# 1-Schematic.net
KiCad netlist of a schematic drawn in EasyEDA
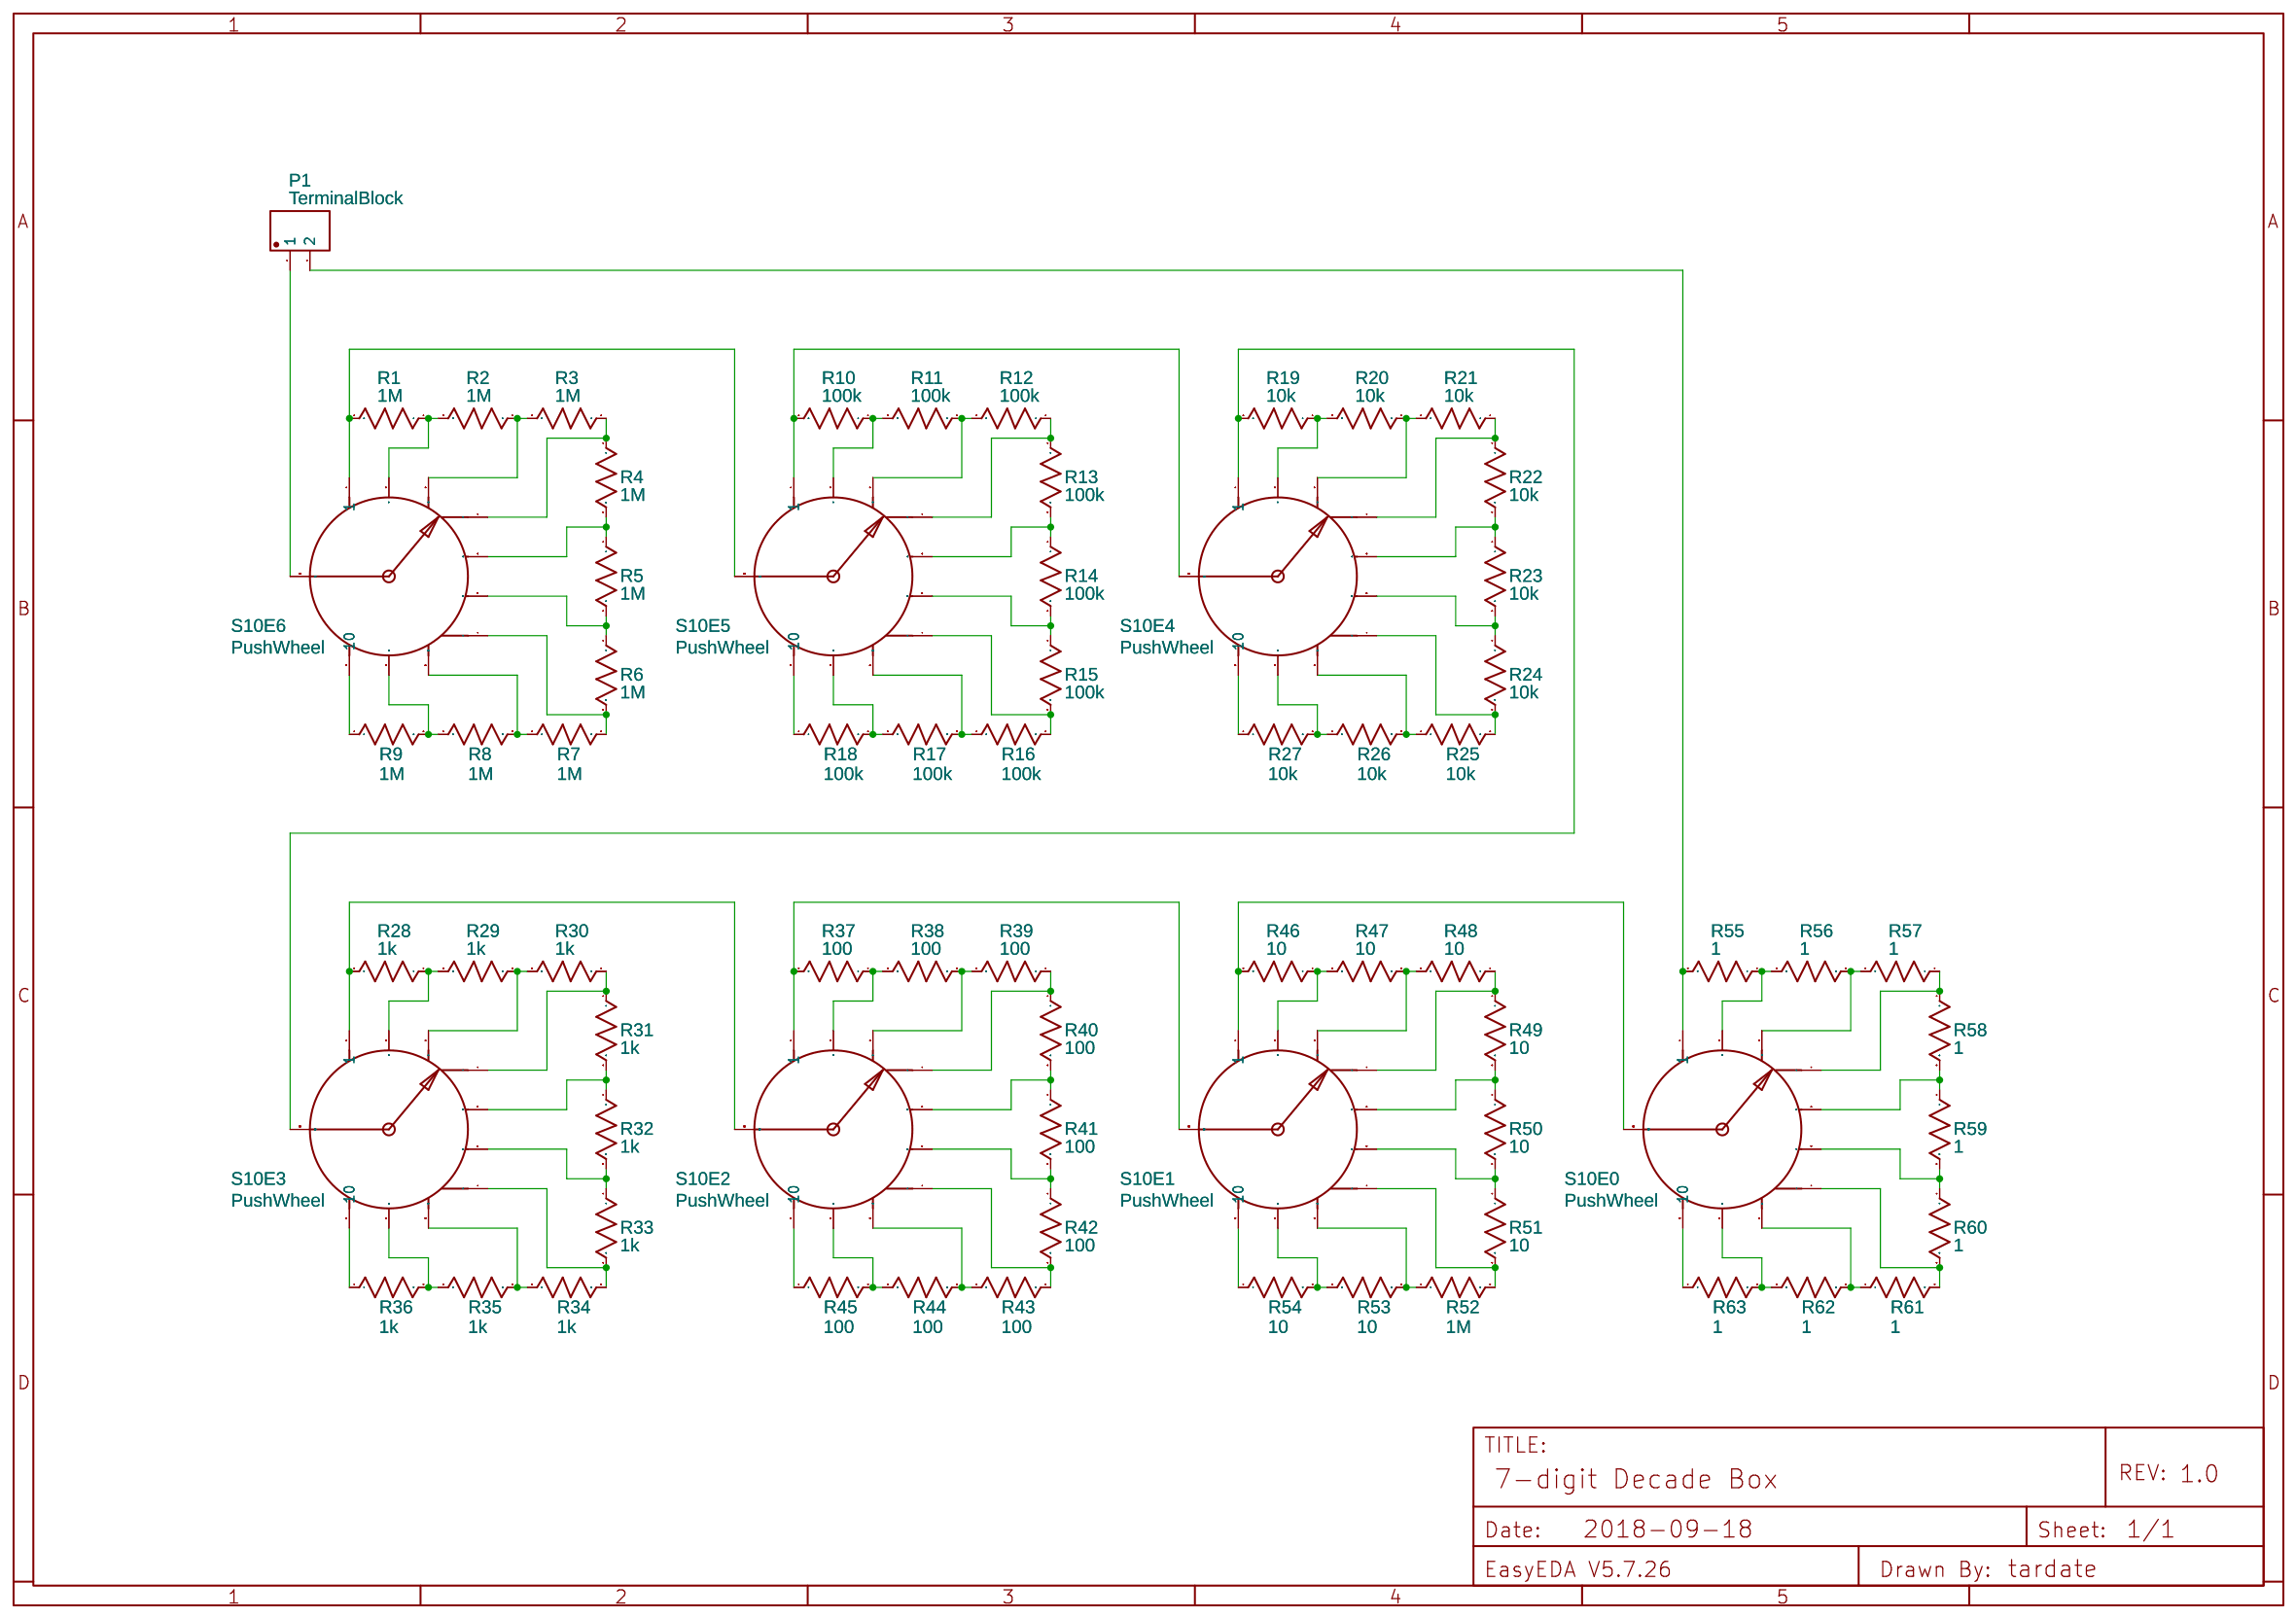
[diagram p0: schematic sheet]

(export (version "E")
  (design (tool "Eeschema 10.0.6"))
  (components
    (comp (ref "P1")
      (value "TerminalBlock")
      (fields
        (field (name "BOM_Manufacturer Part") "WJ2EDGVC-5.08-2P")
        (field (name "BOM_Supplier Part") "C8445")
      )
      (libsource (lib "") (part "Unknown_145_115"))
    )
    (comp (ref "R1")
      (value "1M")
      (fields (field (name "BOM_Manufacturer Part") "?"))
      (libsource (lib "") (part "Res_AXIAL-0.3(1/8W)_US"))
    )
    (comp (ref "R2")
      (value "1M")
      (fields (field (name "BOM_Manufacturer Part") "?"))
      (libsource (lib "") (part "Res_AXIAL-0.3(1/8W)_US"))
    )
    (comp (ref "R3")
      (value "1M")
      (fields (field (name "BOM_Manufacturer Part") "?"))
      (libsource (lib "") (part "Res_AXIAL-0.3(1/8W)_US"))
    )
    (comp (ref "R4")
      (value "1M")
      (fields (field (name "BOM_Manufacturer Part") "?"))
      (libsource (lib "") (part "Res_AXIAL-0.3(1/8W)_US_2"))
    )
    (comp (ref "R5")
      (value "1M")
      (fields (field (name "BOM_Manufacturer Part") "?"))
      (libsource (lib "") (part "Res_AXIAL-0.3(1/8W)_US_2"))
    )
    (comp (ref "R6")
      (value "1M")
      (fields (field (name "BOM_Manufacturer Part") "?"))
      (libsource (lib "") (part "Res_AXIAL-0.3(1/8W)_US_2"))
    )
    (comp (ref "R7")
      (value "1M")
      (fields (field (name "BOM_Manufacturer Part") "?"))
      (libsource (lib "") (part "Res_AXIAL-0.3(1/8W)_US_1"))
    )
    (comp (ref "R8")
      (value "1M")
      (fields (field (name "BOM_Manufacturer Part") "?"))
      (libsource (lib "") (part "Res_AXIAL-0.3(1/8W)_US_1"))
    )
    (comp (ref "R9")
      (value "1M")
      (fields (field (name "BOM_Manufacturer Part") "?"))
      (libsource (lib "") (part "Res_AXIAL-0.3(1/8W)_US_1"))
    )
    (comp (ref "R10")
      (value "100k")
      (fields (field (name "BOM_Manufacturer Part") "?"))
      (libsource (lib "") (part "Res_AXIAL-0.3(1/8W)_US"))
    )
    (comp (ref "R11")
      (value "100k")
      (fields (field (name "BOM_Manufacturer Part") "?"))
      (libsource (lib "") (part "Res_AXIAL-0.3(1/8W)_US"))
    )
    (comp (ref "R12")
      (value "100k")
      (fields (field (name "BOM_Manufacturer Part") "?"))
      (libsource (lib "") (part "Res_AXIAL-0.3(1/8W)_US"))
    )
    (comp (ref "R13")
      (value "100k")
      (fields (field (name "BOM_Manufacturer Part") "?"))
      (libsource (lib "") (part "Res_AXIAL-0.3(1/8W)_US_2"))
    )
    (comp (ref "R14")
      (value "100k")
      (fields (field (name "BOM_Manufacturer Part") "?"))
      (libsource (lib "") (part "Res_AXIAL-0.3(1/8W)_US_2"))
    )
    (comp (ref "R15")
      (value "100k")
      (fields (field (name "BOM_Manufacturer Part") "?"))
      (libsource (lib "") (part "Res_AXIAL-0.3(1/8W)_US_2"))
    )
    (comp (ref "R16")
      (value "100k")
      (fields (field (name "BOM_Manufacturer Part") "?"))
      (libsource (lib "") (part "Res_AXIAL-0.3(1/8W)_US_1"))
    )
    (comp (ref "R17")
      (value "100k")
      (fields (field (name "BOM_Manufacturer Part") "?"))
      (libsource (lib "") (part "Res_AXIAL-0.3(1/8W)_US_1"))
    )
    (comp (ref "R18")
      (value "100k")
      (fields (field (name "BOM_Manufacturer Part") "?"))
      (libsource (lib "") (part "Res_AXIAL-0.3(1/8W)_US_1"))
    )
    (comp (ref "R19")
      (value "10k")
      (fields (field (name "BOM_Manufacturer Part") "?"))
      (libsource (lib "") (part "Res_AXIAL-0.3(1/8W)_US"))
    )
    (comp (ref "R20")
      (value "10k")
      (fields (field (name "BOM_Manufacturer Part") "?"))
      (libsource (lib "") (part "Res_AXIAL-0.3(1/8W)_US"))
    )
    (comp (ref "R21")
      (value "10k")
      (fields (field (name "BOM_Manufacturer Part") "?"))
      (libsource (lib "") (part "Res_AXIAL-0.3(1/8W)_US"))
    )
    (comp (ref "R22")
      (value "10k")
      (fields (field (name "BOM_Manufacturer Part") "?"))
      (libsource (lib "") (part "Res_AXIAL-0.3(1/8W)_US_2"))
    )
    (comp (ref "R23")
      (value "10k")
      (fields (field (name "BOM_Manufacturer Part") "?"))
      (libsource (lib "") (part "Res_AXIAL-0.3(1/8W)_US_2"))
    )
    (comp (ref "R24")
      (value "10k")
      (fields (field (name "BOM_Manufacturer Part") "?"))
      (libsource (lib "") (part "Res_AXIAL-0.3(1/8W)_US_2"))
    )
    (comp (ref "R25")
      (value "10k")
      (fields (field (name "BOM_Manufacturer Part") "?"))
      (libsource (lib "") (part "Res_AXIAL-0.3(1/8W)_US_1"))
    )
    (comp (ref "R26")
      (value "10k")
      (fields (field (name "BOM_Manufacturer Part") "?"))
      (libsource (lib "") (part "Res_AXIAL-0.3(1/8W)_US_1"))
    )
    (comp (ref "R27")
      (value "10k")
      (fields (field (name "BOM_Manufacturer Part") "?"))
      (libsource (lib "") (part "Res_AXIAL-0.3(1/8W)_US_1"))
    )
    (comp (ref "R28")
      (value "1k")
      (fields (field (name "BOM_Manufacturer Part") "?"))
      (libsource (lib "") (part "Res_AXIAL-0.3(1/8W)_US"))
    )
    (comp (ref "R29")
      (value "1k")
      (fields (field (name "BOM_Manufacturer Part") "?"))
      (libsource (lib "") (part "Res_AXIAL-0.3(1/8W)_US"))
    )
    (comp (ref "R30")
      (value "1k")
      (fields (field (name "BOM_Manufacturer Part") "?"))
      (libsource (lib "") (part "Res_AXIAL-0.3(1/8W)_US"))
    )
    (comp (ref "R31")
      (value "1k")
      (fields (field (name "BOM_Manufacturer Part") "?"))
      (libsource (lib "") (part "Res_AXIAL-0.3(1/8W)_US_2"))
    )
    (comp (ref "R32")
      (value "1k")
      (fields (field (name "BOM_Manufacturer Part") "?"))
      (libsource (lib "") (part "Res_AXIAL-0.3(1/8W)_US_2"))
    )
    (comp (ref "R33")
      (value "1k")
      (fields (field (name "BOM_Manufacturer Part") "?"))
      (libsource (lib "") (part "Res_AXIAL-0.3(1/8W)_US_2"))
    )
    (comp (ref "R34")
      (value "1k")
      (fields (field (name "BOM_Manufacturer Part") "?"))
      (libsource (lib "") (part "Res_AXIAL-0.3(1/8W)_US_1"))
    )
    (comp (ref "R35")
      (value "1k")
      (fields (field (name "BOM_Manufacturer Part") "?"))
      (libsource (lib "") (part "Res_AXIAL-0.3(1/8W)_US_1"))
    )
    (comp (ref "R36")
      (value "1k")
      (fields (field (name "BOM_Manufacturer Part") "?"))
      (libsource (lib "") (part "Res_AXIAL-0.3(1/8W)_US_1"))
    )
    (comp (ref "R37")
      (value "100")
      (fields (field (name "BOM_Manufacturer Part") "?"))
      (libsource (lib "") (part "Res_AXIAL-0.3(1/8W)_US"))
    )
    (comp (ref "R38")
      (value "100")
      (fields (field (name "BOM_Manufacturer Part") "?"))
      (libsource (lib "") (part "Res_AXIAL-0.3(1/8W)_US"))
    )
    (comp (ref "R39")
      (value "100")
      (fields (field (name "BOM_Manufacturer Part") "?"))
      (libsource (lib "") (part "Res_AXIAL-0.3(1/8W)_US"))
    )
    (comp (ref "R40")
      (value "100")
      (fields (field (name "BOM_Manufacturer Part") "?"))
      (libsource (lib "") (part "Res_AXIAL-0.3(1/8W)_US_2"))
    )
    (comp (ref "R41")
      (value "100")
      (fields (field (name "BOM_Manufacturer Part") "?"))
      (libsource (lib "") (part "Res_AXIAL-0.3(1/8W)_US_2"))
    )
    (comp (ref "R42")
      (value "100")
      (fields (field (name "BOM_Manufacturer Part") "?"))
      (libsource (lib "") (part "Res_AXIAL-0.3(1/8W)_US_2"))
    )
    (comp (ref "R43")
      (value "100")
      (fields (field (name "BOM_Manufacturer Part") "?"))
      (libsource (lib "") (part "Res_AXIAL-0.3(1/8W)_US_1"))
    )
    (comp (ref "R44")
      (value "100")
      (fields (field (name "BOM_Manufacturer Part") "?"))
      (libsource (lib "") (part "Res_AXIAL-0.3(1/8W)_US_1"))
    )
    (comp (ref "R45")
      (value "100")
      (fields (field (name "BOM_Manufacturer Part") "?"))
      (libsource (lib "") (part "Res_AXIAL-0.3(1/8W)_US_1"))
    )
    (comp (ref "R46")
      (value "10")
      (fields (field (name "BOM_Manufacturer Part") "?"))
      (libsource (lib "") (part "Res_AXIAL-0.3(1/8W)_US"))
    )
    (comp (ref "R47")
      (value "10")
      (fields (field (name "BOM_Manufacturer Part") "?"))
      (libsource (lib "") (part "Res_AXIAL-0.3(1/8W)_US"))
    )
    (comp (ref "R48")
      (value "10")
      (fields (field (name "BOM_Manufacturer Part") "?"))
      (libsource (lib "") (part "Res_AXIAL-0.3(1/8W)_US"))
    )
    (comp (ref "R49")
      (value "10")
      (fields (field (name "BOM_Manufacturer Part") "?"))
      (libsource (lib "") (part "Res_AXIAL-0.3(1/8W)_US_2"))
    )
    (comp (ref "R50")
      (value "10")
      (fields (field (name "BOM_Manufacturer Part") "?"))
      (libsource (lib "") (part "Res_AXIAL-0.3(1/8W)_US_2"))
    )
    (comp (ref "R51")
      (value "10")
      (fields (field (name "BOM_Manufacturer Part") "?"))
      (libsource (lib "") (part "Res_AXIAL-0.3(1/8W)_US_2"))
    )
    (comp (ref "R52")
      (value "1M")
      (fields (field (name "BOM_Manufacturer Part") "?"))
      (libsource (lib "") (part "Res_AXIAL-0.3(1/8W)_US_1"))
    )
    (comp (ref "R53")
      (value "10")
      (fields (field (name "BOM_Manufacturer Part") "?"))
      (libsource (lib "") (part "Res_AXIAL-0.3(1/8W)_US_1"))
    )
    (comp (ref "R54")
      (value "10")
      (fields (field (name "BOM_Manufacturer Part") "?"))
      (libsource (lib "") (part "Res_AXIAL-0.3(1/8W)_US_1"))
    )
    (comp (ref "R55")
      (value "1")
      (fields (field (name "BOM_Manufacturer Part") "?"))
      (libsource (lib "") (part "Res_AXIAL-0.3(1/8W)_US"))
    )
    (comp (ref "R56")
      (value "1")
      (fields (field (name "BOM_Manufacturer Part") "?"))
      (libsource (lib "") (part "Res_AXIAL-0.3(1/8W)_US"))
    )
    (comp (ref "R57")
      (value "1")
      (fields (field (name "BOM_Manufacturer Part") "?"))
      (libsource (lib "") (part "Res_AXIAL-0.3(1/8W)_US"))
    )
    (comp (ref "R58")
      (value "1")
      (fields (field (name "BOM_Manufacturer Part") "?"))
      (libsource (lib "") (part "Res_AXIAL-0.3(1/8W)_US_2"))
    )
    (comp (ref "R59")
      (value "1")
      (fields (field (name "BOM_Manufacturer Part") "?"))
      (libsource (lib "") (part "Res_AXIAL-0.3(1/8W)_US_2"))
    )
    (comp (ref "R60")
      (value "1")
      (fields (field (name "BOM_Manufacturer Part") "?"))
      (libsource (lib "") (part "Res_AXIAL-0.3(1/8W)_US_2"))
    )
    (comp (ref "R61")
      (value "1")
      (fields (field (name "BOM_Manufacturer Part") "?"))
      (libsource (lib "") (part "Res_AXIAL-0.3(1/8W)_US_1"))
    )
    (comp (ref "R62")
      (value "1")
      (fields (field (name "BOM_Manufacturer Part") "?"))
      (libsource (lib "") (part "Res_AXIAL-0.3(1/8W)_US_1"))
    )
    (comp (ref "R63")
      (value "1")
      (fields (field (name "BOM_Manufacturer Part") "?"))
      (libsource (lib "") (part "Res_AXIAL-0.3(1/8W)_US_1"))
    )
    (comp (ref "S10E0")
      (value "PushWheel")
      (fields (field (name "BOM_Manufacturer Part") "?"))
      (libsource (lib "") (part "Unknown_865_565"))
    )
    (comp (ref "S10E1")
      (value "PushWheel")
      (fields (field (name "BOM_Manufacturer Part") "?"))
      (libsource (lib "") (part "Unknown_640_565"))
    )
    (comp (ref "S10E2")
      (value "PushWheel")
      (fields (field (name "BOM_Manufacturer Part") "?"))
      (libsource (lib "") (part "Unknown_415_565"))
    )
    (comp (ref "S10E3")
      (value "PushWheel")
      (fields (field (name "BOM_Manufacturer Part") "?"))
      (libsource (lib "") (part "Unknown_190_565"))
    )
    (comp (ref "S10E4")
      (value "PushWheel")
      (fields (field (name "BOM_Manufacturer Part") "?"))
      (libsource (lib "") (part "Unknown_640_285"))
    )
    (comp (ref "S10E5")
      (value "PushWheel")
      (fields (field (name "BOM_Manufacturer Part") "?"))
      (libsource (lib "") (part "Unknown_415_285"))
    )
    (comp (ref "S10E6")
      (value "PushWheel")
      (fields (field (name "BOM_Manufacturer Part") "?"))
      (libsource (lib "") (part "Unknown_190_285"))
    )
  )
  (nets
    (net (code "1") (name "Net-(P1-Pad1)") (class "Default")
      (node (ref "P1") (pin "1") (pinfunction "1_1") (pintype "unspecified"))
      (node (ref "S10E6") (pin "COMMON") (pinfunction "COMMON_COMMON") (pintype "unspecified"))
    )
    (net (code "2") (name "Net-(P1-Pad2)") (class "Default")
      (node (ref "P1") (pin "2") (pinfunction "2_2") (pintype "unspecified"))
      (node (ref "R55") (pin "2") (pinfunction "2_2") (pintype "unspecified"))
      (node (ref "S10E0") (pin "1") (pinfunction "1_1") (pintype "unspecified"))
    )
    (net (code "3") (name "Net-(R1-Pad1)") (class "Default")
      (node (ref "R1") (pin "1") (pinfunction "1_1") (pintype "unspecified"))
      (node (ref "R2") (pin "2") (pinfunction "2_2") (pintype "unspecified"))
      (node (ref "S10E6") (pin "2") (pinfunction "2_2") (pintype "unspecified"))
    )
    (net (code "4") (name "Net-(R1-Pad2)") (class "Default")
      (node (ref "R1") (pin "2") (pinfunction "2_2") (pintype "unspecified"))
      (node (ref "S10E5") (pin "COMMON") (pinfunction "COMMON_COMMON") (pintype "unspecified"))
      (node (ref "S10E6") (pin "1") (pinfunction "1_1") (pintype "unspecified"))
    )
    (net (code "5") (name "Net-(R2-Pad1)") (class "Default")
      (node (ref "R2") (pin "1") (pinfunction "1_1") (pintype "unspecified"))
      (node (ref "R3") (pin "2") (pinfunction "2_2") (pintype "unspecified"))
      (node (ref "S10E6") (pin "3") (pinfunction "3_3") (pintype "unspecified"))
    )
    (net (code "6") (name "Net-(R3-Pad1)") (class "Default")
      (node (ref "R3") (pin "1") (pinfunction "1_1") (pintype "unspecified"))
      (node (ref "R4") (pin "1") (pinfunction "1_1") (pintype "unspecified"))
      (node (ref "S10E6") (pin "4") (pinfunction "4_4") (pintype "unspecified"))
    )
    (net (code "7") (name "Net-(R4-Pad2)") (class "Default")
      (node (ref "R4") (pin "2") (pinfunction "2_2") (pintype "unspecified"))
      (node (ref "R5") (pin "1") (pinfunction "1_1") (pintype "unspecified"))
      (node (ref "S10E6") (pin "5") (pinfunction "5_5") (pintype "unspecified"))
    )
    (net (code "8") (name "Net-(R5-Pad2)") (class "Default")
      (node (ref "R5") (pin "2") (pinfunction "2_2") (pintype "unspecified"))
      (node (ref "R6") (pin "1") (pinfunction "1_1") (pintype "unspecified"))
      (node (ref "S10E6") (pin "6") (pinfunction "6_6") (pintype "unspecified"))
    )
    (net (code "9") (name "Net-(R6-Pad2)") (class "Default")
      (node (ref "R6") (pin "2") (pinfunction "2_2") (pintype "unspecified"))
      (node (ref "R7") (pin "2") (pinfunction "2_2") (pintype "unspecified"))
      (node (ref "S10E6") (pin "7") (pinfunction "7_7") (pintype "unspecified"))
    )
    (net (code "10") (name "Net-(R7-Pad1)") (class "Default")
      (node (ref "R7") (pin "1") (pinfunction "1_1") (pintype "unspecified"))
      (node (ref "R8") (pin "2") (pinfunction "2_2") (pintype "unspecified"))
      (node (ref "S10E6") (pin "8") (pinfunction "8_8") (pintype "unspecified"))
    )
    (net (code "11") (name "Net-(R8-Pad1)") (class "Default")
      (node (ref "R8") (pin "1") (pinfunction "1_1") (pintype "unspecified"))
      (node (ref "R9") (pin "2") (pinfunction "2_2") (pintype "unspecified"))
      (node (ref "S10E6") (pin "9") (pinfunction "9_9") (pintype "unspecified"))
    )
    (net (code "12") (name "Net-(R9-Pad1)") (class "Default")
      (node (ref "R9") (pin "1") (pinfunction "1_1") (pintype "unspecified"))
      (node (ref "S10E6") (pin "10") (pinfunction "10_10") (pintype "unspecified"))
    )
    (net (code "13") (name "Net-(R10-Pad1)") (class "Default")
      (node (ref "R10") (pin "1") (pinfunction "1_1") (pintype "unspecified"))
      (node (ref "R11") (pin "2") (pinfunction "2_2") (pintype "unspecified"))
      (node (ref "S10E5") (pin "2") (pinfunction "2_2") (pintype "unspecified"))
    )
    (net (code "14") (name "Net-(R10-Pad2)") (class "Default")
      (node (ref "R10") (pin "2") (pinfunction "2_2") (pintype "unspecified"))
      (node (ref "S10E4") (pin "COMMON") (pinfunction "COMMON_COMMON") (pintype "unspecified"))
      (node (ref "S10E5") (pin "1") (pinfunction "1_1") (pintype "unspecified"))
    )
    (net (code "15") (name "Net-(R11-Pad1)") (class "Default")
      (node (ref "R11") (pin "1") (pinfunction "1_1") (pintype "unspecified"))
      (node (ref "R12") (pin "2") (pinfunction "2_2") (pintype "unspecified"))
      (node (ref "S10E5") (pin "3") (pinfunction "3_3") (pintype "unspecified"))
    )
    (net (code "16") (name "Net-(R12-Pad1)") (class "Default")
      (node (ref "R12") (pin "1") (pinfunction "1_1") (pintype "unspecified"))
      (node (ref "R13") (pin "1") (pinfunction "1_1") (pintype "unspecified"))
      (node (ref "S10E5") (pin "4") (pinfunction "4_4") (pintype "unspecified"))
    )
    (net (code "17") (name "Net-(R13-Pad2)") (class "Default")
      (node (ref "R13") (pin "2") (pinfunction "2_2") (pintype "unspecified"))
      (node (ref "R14") (pin "1") (pinfunction "1_1") (pintype "unspecified"))
      (node (ref "S10E5") (pin "5") (pinfunction "5_5") (pintype "unspecified"))
    )
    (net (code "18") (name "Net-(R14-Pad2)") (class "Default")
      (node (ref "R14") (pin "2") (pinfunction "2_2") (pintype "unspecified"))
      (node (ref "R15") (pin "1") (pinfunction "1_1") (pintype "unspecified"))
      (node (ref "S10E5") (pin "6") (pinfunction "6_6") (pintype "unspecified"))
    )
    (net (code "19") (name "Net-(R15-Pad2)") (class "Default")
      (node (ref "R15") (pin "2") (pinfunction "2_2") (pintype "unspecified"))
      (node (ref "R16") (pin "2") (pinfunction "2_2") (pintype "unspecified"))
      (node (ref "S10E5") (pin "7") (pinfunction "7_7") (pintype "unspecified"))
    )
    (net (code "20") (name "Net-(R16-Pad1)") (class "Default")
      (node (ref "R16") (pin "1") (pinfunction "1_1") (pintype "unspecified"))
      (node (ref "R17") (pin "2") (pinfunction "2_2") (pintype "unspecified"))
      (node (ref "S10E5") (pin "8") (pinfunction "8_8") (pintype "unspecified"))
    )
    (net (code "21") (name "Net-(R17-Pad1)") (class "Default")
      (node (ref "R17") (pin "1") (pinfunction "1_1") (pintype "unspecified"))
      (node (ref "R18") (pin "2") (pinfunction "2_2") (pintype "unspecified"))
      (node (ref "S10E5") (pin "9") (pinfunction "9_9") (pintype "unspecified"))
    )
    (net (code "22") (name "Net-(R18-Pad1)") (class "Default")
      (node (ref "R18") (pin "1") (pinfunction "1_1") (pintype "unspecified"))
      (node (ref "S10E5") (pin "10") (pinfunction "10_10") (pintype "unspecified"))
    )
    (net (code "23") (name "Net-(R19-Pad1)") (class "Default")
      (node (ref "R19") (pin "1") (pinfunction "1_1") (pintype "unspecified"))
      (node (ref "R20") (pin "2") (pinfunction "2_2") (pintype "unspecified"))
      (node (ref "S10E4") (pin "2") (pinfunction "2_2") (pintype "unspecified"))
    )
    (net (code "24") (name "Net-(R19-Pad2)") (class "Default")
      (node (ref "R19") (pin "2") (pinfunction "2_2") (pintype "unspecified"))
      (node (ref "S10E3") (pin "COMMON") (pinfunction "COMMON_COMMON") (pintype "unspecified"))
      (node (ref "S10E4") (pin "1") (pinfunction "1_1") (pintype "unspecified"))
    )
    (net (code "25") (name "Net-(R20-Pad1)") (class "Default")
      (node (ref "R20") (pin "1") (pinfunction "1_1") (pintype "unspecified"))
      (node (ref "R21") (pin "2") (pinfunction "2_2") (pintype "unspecified"))
      (node (ref "S10E4") (pin "3") (pinfunction "3_3") (pintype "unspecified"))
    )
    (net (code "26") (name "Net-(R21-Pad1)") (class "Default")
      (node (ref "R21") (pin "1") (pinfunction "1_1") (pintype "unspecified"))
      (node (ref "R22") (pin "1") (pinfunction "1_1") (pintype "unspecified"))
      (node (ref "S10E4") (pin "4") (pinfunction "4_4") (pintype "unspecified"))
    )
    (net (code "27") (name "Net-(R22-Pad2)") (class "Default")
      (node (ref "R22") (pin "2") (pinfunction "2_2") (pintype "unspecified"))
      (node (ref "R23") (pin "1") (pinfunction "1_1") (pintype "unspecified"))
      (node (ref "S10E4") (pin "5") (pinfunction "5_5") (pintype "unspecified"))
    )
    (net (code "28") (name "Net-(R23-Pad2)") (class "Default")
      (node (ref "R23") (pin "2") (pinfunction "2_2") (pintype "unspecified"))
      (node (ref "R24") (pin "1") (pinfunction "1_1") (pintype "unspecified"))
      (node (ref "S10E4") (pin "6") (pinfunction "6_6") (pintype "unspecified"))
    )
    (net (code "29") (name "Net-(R24-Pad2)") (class "Default")
      (node (ref "R24") (pin "2") (pinfunction "2_2") (pintype "unspecified"))
      (node (ref "R25") (pin "2") (pinfunction "2_2") (pintype "unspecified"))
      (node (ref "S10E4") (pin "7") (pinfunction "7_7") (pintype "unspecified"))
    )
    (net (code "30") (name "Net-(R25-Pad1)") (class "Default")
      (node (ref "R25") (pin "1") (pinfunction "1_1") (pintype "unspecified"))
      (node (ref "R26") (pin "2") (pinfunction "2_2") (pintype "unspecified"))
      (node (ref "S10E4") (pin "8") (pinfunction "8_8") (pintype "unspecified"))
    )
    (net (code "31") (name "Net-(R26-Pad1)") (class "Default")
      (node (ref "R26") (pin "1") (pinfunction "1_1") (pintype "unspecified"))
      (node (ref "R27") (pin "2") (pinfunction "2_2") (pintype "unspecified"))
      (node (ref "S10E4") (pin "9") (pinfunction "9_9") (pintype "unspecified"))
    )
    (net (code "32") (name "Net-(R27-Pad1)") (class "Default")
      (node (ref "R27") (pin "1") (pinfunction "1_1") (pintype "unspecified"))
      (node (ref "S10E4") (pin "10") (pinfunction "10_10") (pintype "unspecified"))
    )
    (net (code "33") (name "Net-(R28-Pad1)") (class "Default")
      (node (ref "R28") (pin "1") (pinfunction "1_1") (pintype "unspecified"))
      (node (ref "R29") (pin "2") (pinfunction "2_2") (pintype "unspecified"))
      (node (ref "S10E3") (pin "2") (pinfunction "2_2") (pintype "unspecified"))
    )
    (net (code "34") (name "Net-(R28-Pad2)") (class "Default")
      (node (ref "R28") (pin "2") (pinfunction "2_2") (pintype "unspecified"))
      (node (ref "S10E2") (pin "COMMON") (pinfunction "COMMON_COMMON") (pintype "unspecified"))
      (node (ref "S10E3") (pin "1") (pinfunction "1_1") (pintype "unspecified"))
    )
    (net (code "35") (name "Net-(R29-Pad1)") (class "Default")
      (node (ref "R29") (pin "1") (pinfunction "1_1") (pintype "unspecified"))
      (node (ref "R30") (pin "2") (pinfunction "2_2") (pintype "unspecified"))
      (node (ref "S10E3") (pin "3") (pinfunction "3_3") (pintype "unspecified"))
    )
    (net (code "36") (name "Net-(R30-Pad1)") (class "Default")
      (node (ref "R30") (pin "1") (pinfunction "1_1") (pintype "unspecified"))
      (node (ref "R31") (pin "1") (pinfunction "1_1") (pintype "unspecified"))
      (node (ref "S10E3") (pin "4") (pinfunction "4_4") (pintype "unspecified"))
    )
    (net (code "37") (name "Net-(R31-Pad2)") (class "Default")
      (node (ref "R31") (pin "2") (pinfunction "2_2") (pintype "unspecified"))
      (node (ref "R32") (pin "1") (pinfunction "1_1") (pintype "unspecified"))
      (node (ref "S10E3") (pin "5") (pinfunction "5_5") (pintype "unspecified"))
    )
    (net (code "38") (name "Net-(R32-Pad2)") (class "Default")
      (node (ref "R32") (pin "2") (pinfunction "2_2") (pintype "unspecified"))
      (node (ref "R33") (pin "1") (pinfunction "1_1") (pintype "unspecified"))
      (node (ref "S10E3") (pin "6") (pinfunction "6_6") (pintype "unspecified"))
    )
    (net (code "39") (name "Net-(R33-Pad2)") (class "Default")
      (node (ref "R33") (pin "2") (pinfunction "2_2") (pintype "unspecified"))
      (node (ref "R34") (pin "2") (pinfunction "2_2") (pintype "unspecified"))
      (node (ref "S10E3") (pin "7") (pinfunction "7_7") (pintype "unspecified"))
    )
    (net (code "40") (name "Net-(R34-Pad1)") (class "Default")
      (node (ref "R34") (pin "1") (pinfunction "1_1") (pintype "unspecified"))
      (node (ref "R35") (pin "2") (pinfunction "2_2") (pintype "unspecified"))
      (node (ref "S10E3") (pin "8") (pinfunction "8_8") (pintype "unspecified"))
    )
    (net (code "41") (name "Net-(R35-Pad1)") (class "Default")
      (node (ref "R35") (pin "1") (pinfunction "1_1") (pintype "unspecified"))
      (node (ref "R36") (pin "2") (pinfunction "2_2") (pintype "unspecified"))
      (node (ref "S10E3") (pin "9") (pinfunction "9_9") (pintype "unspecified"))
    )
    (net (code "42") (name "Net-(R36-Pad1)") (class "Default")
      (node (ref "R36") (pin "1") (pinfunction "1_1") (pintype "unspecified"))
      (node (ref "S10E3") (pin "10") (pinfunction "10_10") (pintype "unspecified"))
    )
    (net (code "43") (name "Net-(R37-Pad1)") (class "Default")
      (node (ref "R37") (pin "1") (pinfunction "1_1") (pintype "unspecified"))
      (node (ref "R38") (pin "2") (pinfunction "2_2") (pintype "unspecified"))
      (node (ref "S10E2") (pin "2") (pinfunction "2_2") (pintype "unspecified"))
    )
    (net (code "44") (name "Net-(R37-Pad2)") (class "Default")
      (node (ref "R37") (pin "2") (pinfunction "2_2") (pintype "unspecified"))
      (node (ref "S10E1") (pin "COMMON") (pinfunction "COMMON_COMMON") (pintype "unspecified"))
      (node (ref "S10E2") (pin "1") (pinfunction "1_1") (pintype "unspecified"))
    )
    (net (code "45") (name "Net-(R38-Pad1)") (class "Default")
      (node (ref "R38") (pin "1") (pinfunction "1_1") (pintype "unspecified"))
      (node (ref "R39") (pin "2") (pinfunction "2_2") (pintype "unspecified"))
      (node (ref "S10E2") (pin "3") (pinfunction "3_3") (pintype "unspecified"))
    )
    (net (code "46") (name "Net-(R39-Pad1)") (class "Default")
      (node (ref "R39") (pin "1") (pinfunction "1_1") (pintype "unspecified"))
      (node (ref "R40") (pin "1") (pinfunction "1_1") (pintype "unspecified"))
      (node (ref "S10E2") (pin "4") (pinfunction "4_4") (pintype "unspecified"))
    )
    (net (code "47") (name "Net-(R40-Pad2)") (class "Default")
      (node (ref "R40") (pin "2") (pinfunction "2_2") (pintype "unspecified"))
      (node (ref "R41") (pin "1") (pinfunction "1_1") (pintype "unspecified"))
      (node (ref "S10E2") (pin "5") (pinfunction "5_5") (pintype "unspecified"))
    )
    (net (code "48") (name "Net-(R41-Pad2)") (class "Default")
      (node (ref "R41") (pin "2") (pinfunction "2_2") (pintype "unspecified"))
      (node (ref "R42") (pin "1") (pinfunction "1_1") (pintype "unspecified"))
      (node (ref "S10E2") (pin "6") (pinfunction "6_6") (pintype "unspecified"))
    )
    (net (code "49") (name "Net-(R42-Pad2)") (class "Default")
      (node (ref "R42") (pin "2") (pinfunction "2_2") (pintype "unspecified"))
      (node (ref "R43") (pin "2") (pinfunction "2_2") (pintype "unspecified"))
      (node (ref "S10E2") (pin "7") (pinfunction "7_7") (pintype "unspecified"))
    )
    (net (code "50") (name "Net-(R43-Pad1)") (class "Default")
      (node (ref "R43") (pin "1") (pinfunction "1_1") (pintype "unspecified"))
      (node (ref "R44") (pin "2") (pinfunction "2_2") (pintype "unspecified"))
      (node (ref "S10E2") (pin "8") (pinfunction "8_8") (pintype "unspecified"))
    )
    (net (code "51") (name "Net-(R44-Pad1)") (class "Default")
      (node (ref "R44") (pin "1") (pinfunction "1_1") (pintype "unspecified"))
      (node (ref "R45") (pin "2") (pinfunction "2_2") (pintype "unspecified"))
      (node (ref "S10E2") (pin "9") (pinfunction "9_9") (pintype "unspecified"))
    )
    (net (code "52") (name "Net-(R45-Pad1)") (class "Default")
      (node (ref "R45") (pin "1") (pinfunction "1_1") (pintype "unspecified"))
      (node (ref "S10E2") (pin "10") (pinfunction "10_10") (pintype "unspecified"))
    )
    (net (code "53") (name "Net-(R46-Pad1)") (class "Default")
      (node (ref "R46") (pin "1") (pinfunction "1_1") (pintype "unspecified"))
      (node (ref "R47") (pin "2") (pinfunction "2_2") (pintype "unspecified"))
      (node (ref "S10E1") (pin "2") (pinfunction "2_2") (pintype "unspecified"))
    )
    (net (code "54") (name "Net-(R46-Pad2)") (class "Default")
      (node (ref "R46") (pin "2") (pinfunction "2_2") (pintype "unspecified"))
      (node (ref "S10E0") (pin "COMMON") (pinfunction "COMMON_COMMON") (pintype "unspecified"))
      (node (ref "S10E1") (pin "1") (pinfunction "1_1") (pintype "unspecified"))
    )
    (net (code "55") (name "Net-(R47-Pad1)") (class "Default")
      (node (ref "R47") (pin "1") (pinfunction "1_1") (pintype "unspecified"))
      (node (ref "R48") (pin "2") (pinfunction "2_2") (pintype "unspecified"))
      (node (ref "S10E1") (pin "3") (pinfunction "3_3") (pintype "unspecified"))
    )
    (net (code "56") (name "Net-(R48-Pad1)") (class "Default")
      (node (ref "R48") (pin "1") (pinfunction "1_1") (pintype "unspecified"))
      (node (ref "R49") (pin "1") (pinfunction "1_1") (pintype "unspecified"))
      (node (ref "S10E1") (pin "4") (pinfunction "4_4") (pintype "unspecified"))
    )
    (net (code "57") (name "Net-(R49-Pad2)") (class "Default")
      (node (ref "R49") (pin "2") (pinfunction "2_2") (pintype "unspecified"))
      (node (ref "R50") (pin "1") (pinfunction "1_1") (pintype "unspecified"))
      (node (ref "S10E1") (pin "5") (pinfunction "5_5") (pintype "unspecified"))
    )
    (net (code "58") (name "Net-(R50-Pad2)") (class "Default")
      (node (ref "R50") (pin "2") (pinfunction "2_2") (pintype "unspecified"))
      (node (ref "R51") (pin "1") (pinfunction "1_1") (pintype "unspecified"))
      (node (ref "S10E1") (pin "6") (pinfunction "6_6") (pintype "unspecified"))
    )
    (net (code "59") (name "Net-(R51-Pad2)") (class "Default")
      (node (ref "R51") (pin "2") (pinfunction "2_2") (pintype "unspecified"))
      (node (ref "R52") (pin "2") (pinfunction "2_2") (pintype "unspecified"))
      (node (ref "S10E1") (pin "7") (pinfunction "7_7") (pintype "unspecified"))
    )
    (net (code "60") (name "Net-(R52-Pad1)") (class "Default")
      (node (ref "R52") (pin "1") (pinfunction "1_1") (pintype "unspecified"))
      (node (ref "R53") (pin "2") (pinfunction "2_2") (pintype "unspecified"))
      (node (ref "S10E1") (pin "8") (pinfunction "8_8") (pintype "unspecified"))
    )
    (net (code "61") (name "Net-(R53-Pad1)") (class "Default")
      (node (ref "R53") (pin "1") (pinfunction "1_1") (pintype "unspecified"))
      (node (ref "R54") (pin "2") (pinfunction "2_2") (pintype "unspecified"))
      (node (ref "S10E1") (pin "9") (pinfunction "9_9") (pintype "unspecified"))
    )
    (net (code "62") (name "Net-(R54-Pad1)") (class "Default")
      (node (ref "R54") (pin "1") (pinfunction "1_1") (pintype "unspecified"))
      (node (ref "S10E1") (pin "10") (pinfunction "10_10") (pintype "unspecified"))
    )
    (net (code "63") (name "Net-(R55-Pad1)") (class "Default")
      (node (ref "R55") (pin "1") (pinfunction "1_1") (pintype "unspecified"))
      (node (ref "R56") (pin "2") (pinfunction "2_2") (pintype "unspecified"))
      (node (ref "S10E0") (pin "2") (pinfunction "2_2") (pintype "unspecified"))
    )
    (net (code "64") (name "Net-(R56-Pad1)") (class "Default")
      (node (ref "R56") (pin "1") (pinfunction "1_1") (pintype "unspecified"))
      (node (ref "R57") (pin "2") (pinfunction "2_2") (pintype "unspecified"))
      (node (ref "S10E0") (pin "3") (pinfunction "3_3") (pintype "unspecified"))
    )
    (net (code "65") (name "Net-(R57-Pad1)") (class "Default")
      (node (ref "R57") (pin "1") (pinfunction "1_1") (pintype "unspecified"))
      (node (ref "R58") (pin "1") (pinfunction "1_1") (pintype "unspecified"))
      (node (ref "S10E0") (pin "4") (pinfunction "4_4") (pintype "unspecified"))
    )
    (net (code "66") (name "Net-(R58-Pad2)") (class "Default")
      (node (ref "R58") (pin "2") (pinfunction "2_2") (pintype "unspecified"))
      (node (ref "R59") (pin "1") (pinfunction "1_1") (pintype "unspecified"))
      (node (ref "S10E0") (pin "5") (pinfunction "5_5") (pintype "unspecified"))
    )
    (net (code "67") (name "Net-(R59-Pad2)") (class "Default")
      (node (ref "R59") (pin "2") (pinfunction "2_2") (pintype "unspecified"))
      (node (ref "R60") (pin "1") (pinfunction "1_1") (pintype "unspecified"))
      (node (ref "S10E0") (pin "6") (pinfunction "6_6") (pintype "unspecified"))
    )
    (net (code "68") (name "Net-(R60-Pad2)") (class "Default")
      (node (ref "R60") (pin "2") (pinfunction "2_2") (pintype "unspecified"))
      (node (ref "R61") (pin "2") (pinfunction "2_2") (pintype "unspecified"))
      (node (ref "S10E0") (pin "7") (pinfunction "7_7") (pintype "unspecified"))
    )
    (net (code "69") (name "Net-(R61-Pad1)") (class "Default")
      (node (ref "R61") (pin "1") (pinfunction "1_1") (pintype "unspecified"))
      (node (ref "R62") (pin "2") (pinfunction "2_2") (pintype "unspecified"))
      (node (ref "S10E0") (pin "8") (pinfunction "8_8") (pintype "unspecified"))
    )
    (net (code "70") (name "Net-(R62-Pad1)") (class "Default")
      (node (ref "R62") (pin "1") (pinfunction "1_1") (pintype "unspecified"))
      (node (ref "R63") (pin "2") (pinfunction "2_2") (pintype "unspecified"))
      (node (ref "S10E0") (pin "9") (pinfunction "9_9") (pintype "unspecified"))
    )
    (net (code "71") (name "Net-(R63-Pad1)") (class "Default")
      (node (ref "R63") (pin "1") (pinfunction "1_1") (pintype "unspecified"))
      (node (ref "S10E0") (pin "10") (pinfunction "10_10") (pintype "unspecified"))
    )
  )
)
